# Robot-Controller_v11.net
KiCad netlist of a schematic drawn in EAGLE
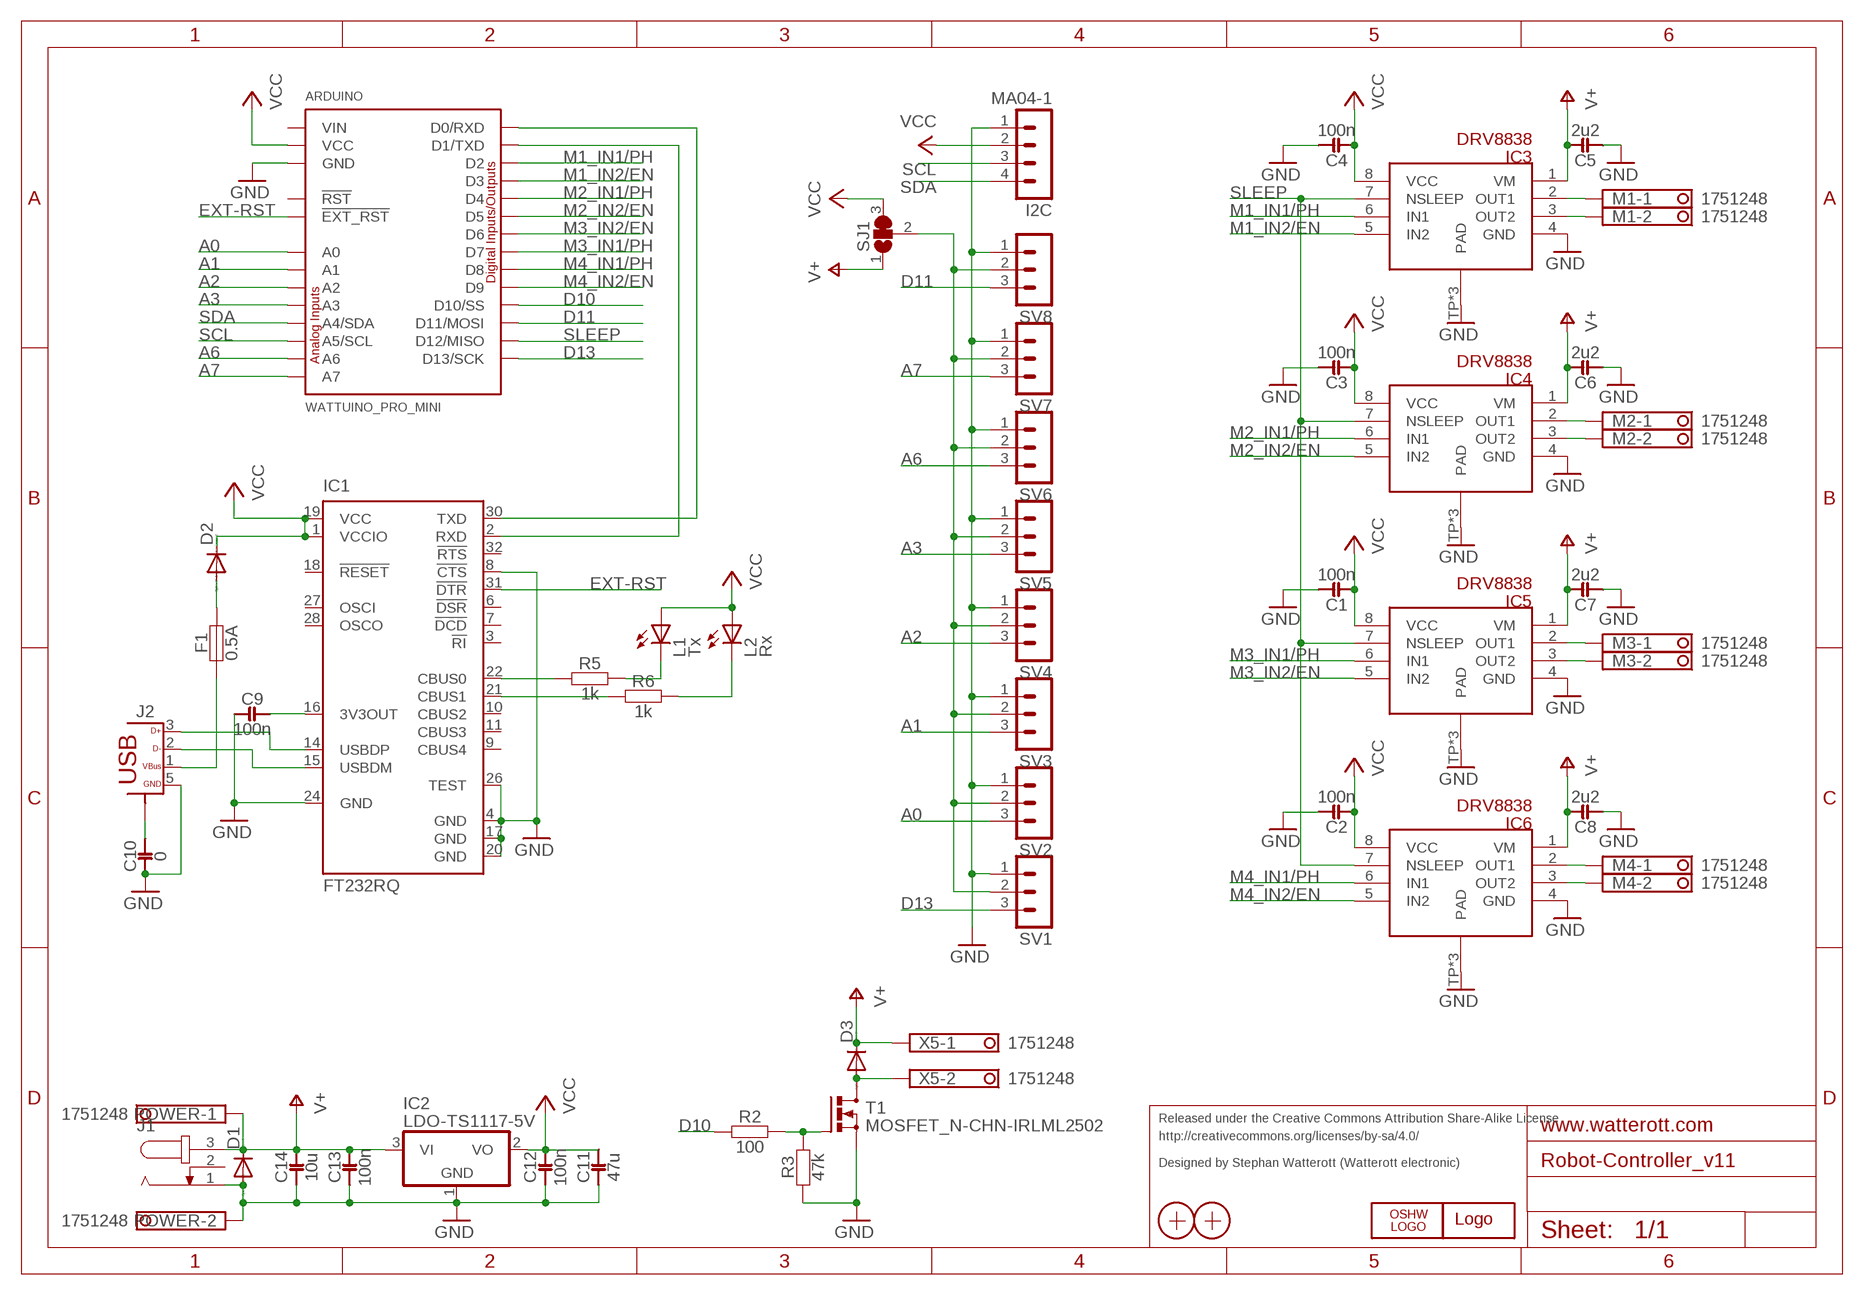
[diagram p0: schematic, sheet 1]

(export (version "E")
  (design (tool "Eeschema 10.0.6"))
  (components
    (comp (ref "ARDUINO")
      (value "WATTUINO_PRO_MINI")
      (footprint "eagle-import:WATTUINO_PRO_MINI")
      (libsource (lib "eagle-import") (part "WATTUINO_PRO_MINIADV1.05"))
    )
    (comp (ref "C1")
      (value "100n")
      (footprint "eagle-import:R0603")
      (libsource (lib "eagle-import") (part "CAPACITOR-C0603"))
    )
    (comp (ref "C2")
      (value "100n")
      (footprint "eagle-import:R0603")
      (libsource (lib "eagle-import") (part "CAPACITOR-C0603"))
    )
    (comp (ref "C3")
      (value "100n")
      (footprint "eagle-import:R0603")
      (libsource (lib "eagle-import") (part "CAPACITOR-C0603"))
    )
    (comp (ref "C4")
      (value "100n")
      (footprint "eagle-import:R0603")
      (libsource (lib "eagle-import") (part "CAPACITOR-C0603"))
    )
    (comp (ref "C5")
      (value "2u2")
      (footprint "eagle-import:R0603")
      (libsource (lib "eagle-import") (part "CAPACITOR-C0603"))
    )
    (comp (ref "C6")
      (value "2u2")
      (footprint "eagle-import:R0603")
      (libsource (lib "eagle-import") (part "CAPACITOR-C0603"))
    )
    (comp (ref "C7")
      (value "2u2")
      (footprint "eagle-import:R0603")
      (libsource (lib "eagle-import") (part "CAPACITOR-C0603"))
    )
    (comp (ref "C8")
      (value "2u2")
      (footprint "eagle-import:R0603")
      (libsource (lib "eagle-import") (part "CAPACITOR-C0603"))
    )
    (comp (ref "C9")
      (value "100n")
      (footprint "eagle-import:R0603")
      (libsource (lib "eagle-import") (part "CAPACITOR-C0603"))
    )
    (comp (ref "C10")
      (value "0")
      (footprint "eagle-import:R0603")
      (libsource (lib "eagle-import") (part "CAPACITOR-C0603"))
    )
    (comp (ref "C11")
      (value "47u")
      (footprint "eagle-import:R1206")
      (libsource (lib "eagle-import") (part "CAPACITOR-C1206"))
    )
    (comp (ref "C12")
      (value "100n")
      (footprint "eagle-import:R0603")
      (libsource (lib "eagle-import") (part "CAPACITOR-C0603"))
    )
    (comp (ref "C13")
      (value "100n")
      (footprint "eagle-import:R0603")
      (libsource (lib "eagle-import") (part "CAPACITOR-C0603"))
    )
    (comp (ref "C14")
      (value "10u")
      (footprint "eagle-import:R1206")
      (libsource (lib "eagle-import") (part "CAPACITOR-C1206"))
    )
    (comp (ref "D1")
      (value "CGRM4001-G")
      (footprint "eagle-import:SOD-123_MINI-SMA")
      (libsource (lib "eagle-import") (part "CGRM400-G1"))
    )
    (comp (ref "D2")
      (value "CGRM4001-G")
      (footprint "eagle-import:SOD-123_MINI-SMA")
      (libsource (lib "eagle-import") (part "CGRM400-G1"))
    )
    (comp (ref "D3")
      (value "CGRM4001-G")
      (footprint "eagle-import:SOD-123_MINI-SMA")
      (libsource (lib "eagle-import") (part "CGRM400-G1"))
    )
    (comp (ref "F1")
      (value "0.5A")
      (footprint "eagle-import:R0805")
      (libsource (lib "eagle-import") (part "RESISTOR-R0805"))
    )
    (comp (ref "I2C")
      (value "MA04-1")
      (footprint "eagle-import:MA04-1")
      (libsource (lib "eagle-import") (part "MA04-1"))
    )
    (comp (ref "IC1")
      (value "FT232RQ")
      (footprint "eagle-import:QFN32")
      (libsource (lib "eagle-import") (part "FT232RQ"))
    )
    (comp (ref "IC2")
      (value "LDO-TS1117-5V")
      (footprint "eagle-import:SOT223")
      (libsource (lib "eagle-import") (part "LDO-TS1117"))
    )
    (comp (ref "IC3")
      (value "DRV8838")
      (footprint "eagle-import:WSON8")
      (libsource (lib "eagle-import") (part "DRV8837"))
    )
    (comp (ref "IC4")
      (value "DRV8838")
      (footprint "eagle-import:WSON8")
      (libsource (lib "eagle-import") (part "DRV8837"))
    )
    (comp (ref "IC5")
      (value "DRV8838")
      (footprint "eagle-import:WSON8")
      (libsource (lib "eagle-import") (part "DRV8837"))
    )
    (comp (ref "IC6")
      (value "DRV8838")
      (footprint "eagle-import:WSON8")
      (libsource (lib "eagle-import") (part "DRV8837"))
    )
    (comp (ref "J1")
      (value "DC-JACK\"\"")
      (footprint "eagle-import:DC-JACK")
      (libsource (lib "eagle-import") (part "DC-JACK{dblquote}{dblquote}"))
    )
    (comp (ref "J2")
      (value "USB10103594-0001LF")
      (footprint "eagle-import:10103594")
      (libsource (lib "eagle-import") (part "USB10103594-0001LF"))
    )
    (comp (ref "L1")
      (value "Tx")
      (footprint "eagle-import:LED_0603")
      (libsource (lib "eagle-import") (part "LED-0603"))
    )
    (comp (ref "L2")
      (value "Rx")
      (footprint "eagle-import:LED_0603")
      (libsource (lib "eagle-import") (part "LED-0603"))
    )
    (comp (ref "LOGO2")
      (value "OSHW_LOGOX0100")
      (footprint "eagle-import:OSHW_6X100")
      (libsource (lib "eagle-import") (part "OSHW_LOGOX0100"))
    )
    (comp (ref "LOGO3")
      (value "LOGO-SPARK_PLACE")
      (footprint "eagle-import:SPARK_TPLACE")
      (libsource (lib "eagle-import") (part "LOGO-SPARK_PLACE"))
    )
    (comp (ref "M1")
      (value "1751248")
      (footprint "eagle-import:1751248")
      (libsource (lib "eagle-import") (part "1751248"))
    )
    (comp (ref "M2")
      (value "1751248")
      (footprint "eagle-import:1751248")
      (libsource (lib "eagle-import") (part "1751248"))
    )
    (comp (ref "M3")
      (value "1751248")
      (footprint "eagle-import:1751248")
      (libsource (lib "eagle-import") (part "1751248"))
    )
    (comp (ref "M4")
      (value "1751248")
      (footprint "eagle-import:1751248")
      (libsource (lib "eagle-import") (part "1751248"))
    )
    (comp (ref "POWER")
      (value "1751248")
      (footprint "eagle-import:1751248")
      (libsource (lib "eagle-import") (part "1751248"))
    )
    (comp (ref "R2")
      (value "100")
      (footprint "eagle-import:R0603")
      (libsource (lib "eagle-import") (part "RESISTOR-R0603"))
    )
    (comp (ref "R3")
      (value "47k")
      (footprint "eagle-import:R0603")
      (libsource (lib "eagle-import") (part "RESISTOR-R0603"))
    )
    (comp (ref "R5")
      (value "1k")
      (footprint "eagle-import:R0603")
      (libsource (lib "eagle-import") (part "RESISTOR-R0603"))
    )
    (comp (ref "R6")
      (value "1k")
      (footprint "eagle-import:R0603")
      (libsource (lib "eagle-import") (part "RESISTOR-R0603"))
    )
    (comp (ref "SJ1")
      (value "SJ2W")
      (footprint "eagle-import:SJ_2")
      (libsource (lib "eagle-import") (part "SJ2W"))
    )
    (comp (ref "SV1")
      (value "MA03-1")
      (footprint "eagle-import:MA03-1")
      (libsource (lib "eagle-import") (part "MA03-1"))
    )
    (comp (ref "SV2")
      (value "MA03-1")
      (footprint "eagle-import:MA03-1")
      (libsource (lib "eagle-import") (part "MA03-1"))
    )
    (comp (ref "SV3")
      (value "MA03-1")
      (footprint "eagle-import:MA03-1")
      (libsource (lib "eagle-import") (part "MA03-1"))
    )
    (comp (ref "SV4")
      (value "MA03-1")
      (footprint "eagle-import:MA03-1")
      (libsource (lib "eagle-import") (part "MA03-1"))
    )
    (comp (ref "SV5")
      (value "MA03-1")
      (footprint "eagle-import:MA03-1")
      (libsource (lib "eagle-import") (part "MA03-1"))
    )
    (comp (ref "SV6")
      (value "MA03-1")
      (footprint "eagle-import:MA03-1")
      (libsource (lib "eagle-import") (part "MA03-1"))
    )
    (comp (ref "SV7")
      (value "MA03-1")
      (footprint "eagle-import:MA03-1")
      (libsource (lib "eagle-import") (part "MA03-1"))
    )
    (comp (ref "SV8")
      (value "MA03-1")
      (footprint "eagle-import:MA03-1")
      (libsource (lib "eagle-import") (part "MA03-1"))
    )
    (comp (ref "T1")
      (value "MOSFET_N-CHN-IRLML2502")
      (footprint "eagle-import:SOT23")
      (libsource (lib "eagle-import") (part "MOSFET_N-CHN-IRLML2502"))
    )
    (comp (ref "X1")
      (value "PASSER-07")
      (footprint "eagle-import:PASSER_07MM")
      (libsource (lib "eagle-import") (part "PASSER-07"))
    )
    (comp (ref "X2")
      (value "PASSER-07")
      (footprint "eagle-import:PASSER_07MM")
      (libsource (lib "eagle-import") (part "PASSER-07"))
    )
    (comp (ref "X5")
      (value "1751248")
      (footprint "eagle-import:1751248")
      (libsource (lib "eagle-import") (part "1751248"))
    )
  )
  (nets
    (net (code "1") (name "/A0") (class "Default")
      (node (ref "ARDUINO") (pin "A0") (pinfunction "A0_A0") (pintype "input"))
      (node (ref "SV2") (pin "3") (pinfunction "3_3") (pintype "passive"))
    )
    (net (code "2") (name "/A1") (class "Default")
      (node (ref "ARDUINO") (pin "A1") (pinfunction "A1_A1") (pintype "input"))
      (node (ref "SV3") (pin "3") (pinfunction "3_3") (pintype "passive"))
    )
    (net (code "3") (name "/A2") (class "Default")
      (node (ref "ARDUINO") (pin "A2") (pinfunction "A2_A2") (pintype "input"))
      (node (ref "SV4") (pin "3") (pinfunction "3_3") (pintype "passive"))
    )
    (net (code "4") (name "/A3") (class "Default")
      (node (ref "ARDUINO") (pin "A3") (pinfunction "A3_A3") (pintype "input"))
      (node (ref "SV5") (pin "3") (pinfunction "3_3") (pintype "passive"))
    )
    (net (code "5") (name "/A6") (class "Default")
      (node (ref "ARDUINO") (pin "A6") (pinfunction "A6_A6") (pintype "input"))
      (node (ref "SV6") (pin "3") (pinfunction "3_3") (pintype "passive"))
    )
    (net (code "6") (name "/A7") (class "Default")
      (node (ref "ARDUINO") (pin "A7") (pinfunction "A7_A7") (pintype "input"))
      (node (ref "SV7") (pin "3") (pinfunction "3_3") (pintype "passive"))
    )
    (net (code "7") (name "/D10") (class "Default")
      (node (ref "ARDUINO") (pin "10") (pinfunction "D10/SS_10") (pintype "bidirectional"))
      (node (ref "R2") (pin "1") (pinfunction "1_1") (pintype "passive"))
    )
    (net (code "8") (name "/D11") (class "Default")
      (node (ref "ARDUINO") (pin "11") (pinfunction "D11/MOSI_11") (pintype "bidirectional"))
      (node (ref "SV8") (pin "3") (pinfunction "3_3") (pintype "passive"))
    )
    (net (code "9") (name "/D13") (class "Default")
      (node (ref "ARDUINO") (pin "13") (pinfunction "D13/SCK_13") (pintype "bidirectional"))
      (node (ref "SV1") (pin "3") (pinfunction "3_3") (pintype "passive"))
    )
    (net (code "10") (name "/EXT-RST") (class "Default")
      (node (ref "ARDUINO") (pin "EXT_RST") (pinfunction "~{EXT_RST}_EXT_RST") (pintype "bidirectional"))
      (node (ref "IC1") (pin "31") (pinfunction "~{DTR}_31") (pintype "output"))
    )
    (net (code "11") (name "/M1_IN1{slash}PH") (class "Default")
      (node (ref "ARDUINO") (pin "2") (pinfunction "D2_2") (pintype "bidirectional"))
      (node (ref "IC3") (pin "6") (pinfunction "IN1_6") (pintype "bidirectional"))
    )
    (net (code "12") (name "/M1_IN2{slash}EN") (class "Default")
      (node (ref "ARDUINO") (pin "3") (pinfunction "D3_3") (pintype "bidirectional"))
      (node (ref "IC3") (pin "5") (pinfunction "IN2_5") (pintype "bidirectional"))
    )
    (net (code "13") (name "/M2_IN1{slash}PH") (class "Default")
      (node (ref "ARDUINO") (pin "4") (pinfunction "D4_4") (pintype "bidirectional"))
      (node (ref "IC4") (pin "6") (pinfunction "IN1_6") (pintype "bidirectional"))
    )
    (net (code "14") (name "/M2_IN2{slash}EN") (class "Default")
      (node (ref "ARDUINO") (pin "5") (pinfunction "D5_5") (pintype "bidirectional"))
      (node (ref "IC4") (pin "5") (pinfunction "IN2_5") (pintype "bidirectional"))
    )
    (net (code "15") (name "/M3_IN1{slash}PH") (class "Default")
      (node (ref "ARDUINO") (pin "7") (pinfunction "D7_7") (pintype "bidirectional"))
      (node (ref "IC5") (pin "6") (pinfunction "IN1_6") (pintype "bidirectional"))
    )
    (net (code "16") (name "/M3_IN2{slash}EN") (class "Default")
      (node (ref "ARDUINO") (pin "6") (pinfunction "D6_6") (pintype "bidirectional"))
      (node (ref "IC5") (pin "5") (pinfunction "IN2_5") (pintype "bidirectional"))
    )
    (net (code "17") (name "/M4_IN1{slash}PH") (class "Default")
      (node (ref "ARDUINO") (pin "8") (pinfunction "D8_8") (pintype "bidirectional"))
      (node (ref "IC6") (pin "6") (pinfunction "IN1_6") (pintype "bidirectional"))
    )
    (net (code "18") (name "/M4_IN2{slash}EN") (class "Default")
      (node (ref "ARDUINO") (pin "9") (pinfunction "D9_9") (pintype "bidirectional"))
      (node (ref "IC6") (pin "5") (pinfunction "IN2_5") (pintype "bidirectional"))
    )
    (net (code "19") (name "/SCL") (class "Default")
      (node (ref "ARDUINO") (pin "A5") (pinfunction "A5/SCL_A5") (pintype "input"))
      (node (ref "I2C") (pin "3") (pinfunction "3_3") (pintype "passive"))
    )
    (net (code "20") (name "/SDA") (class "Default")
      (node (ref "ARDUINO") (pin "A4") (pinfunction "A4/SDA_A4") (pintype "input"))
      (node (ref "I2C") (pin "4") (pinfunction "4_4") (pintype "passive"))
    )
    (net (code "21") (name "/SLEEP") (class "Default")
      (node (ref "ARDUINO") (pin "12") (pinfunction "D12/MISO_12") (pintype "bidirectional"))
      (node (ref "IC3") (pin "7") (pinfunction "NSLEEP_7") (pintype "bidirectional"))
      (node (ref "IC4") (pin "7") (pinfunction "NSLEEP_7") (pintype "bidirectional"))
      (node (ref "IC5") (pin "7") (pinfunction "NSLEEP_7") (pintype "bidirectional"))
      (node (ref "IC6") (pin "7") (pinfunction "NSLEEP_7") (pintype "bidirectional"))
    )
    (net (code "22") (name "/VIN") (class "Default")
      (node (ref "ARDUINO") (pin "VIN") (pinfunction "VIN_VIN") (pintype "power_in"))
    )
    (net (code "23") (name "GND") (class "Default")
      (node (ref "ARDUINO") (pin "GND@1") (pinfunction "GND_GND@1") (pintype "power_in"))
      (node (ref "C1") (pin "2") (pinfunction "2_2") (pintype "passive"))
      (node (ref "C10") (pin "1") (pinfunction "1_1") (pintype "passive"))
      (node (ref "C11") (pin "1") (pinfunction "1_1") (pintype "passive"))
      (node (ref "C12") (pin "1") (pinfunction "1_1") (pintype "passive"))
      (node (ref "C13") (pin "1") (pinfunction "1_1") (pintype "passive"))
      (node (ref "C14") (pin "1") (pinfunction "1_1") (pintype "passive"))
      (node (ref "C2") (pin "2") (pinfunction "2_2") (pintype "passive"))
      (node (ref "C3") (pin "2") (pinfunction "2_2") (pintype "passive"))
      (node (ref "C4") (pin "2") (pinfunction "2_2") (pintype "passive"))
      (node (ref "C5") (pin "1") (pinfunction "1_1") (pintype "passive"))
      (node (ref "C6") (pin "1") (pinfunction "1_1") (pintype "passive"))
      (node (ref "C7") (pin "1") (pinfunction "1_1") (pintype "passive"))
      (node (ref "C8") (pin "1") (pinfunction "1_1") (pintype "passive"))
      (node (ref "C9") (pin "1") (pinfunction "1_1") (pintype "passive"))
      (node (ref "D1") (pin "A") (pinfunction "A_A") (pintype "passive"))
      (node (ref "I2C") (pin "1") (pinfunction "1_1") (pintype "passive"))
      (node (ref "IC1") (pin "17") (pinfunction "GND_17") (pintype "power_in"))
      (node (ref "IC1") (pin "20") (pinfunction "GND_20") (pintype "power_in"))
      (node (ref "IC1") (pin "24") (pinfunction "GND_24") (pintype "power_in"))
      (node (ref "IC1") (pin "26") (pinfunction "TEST_26") (pintype "input"))
      (node (ref "IC1") (pin "4") (pinfunction "GND_4") (pintype "power_in"))
      (node (ref "IC1") (pin "8") (pinfunction "~{CTS}_8") (pintype "input"))
      (node (ref "IC2") (pin "1") (pinfunction "GND_1") (pintype "passive"))
      (node (ref "IC3") (pin "4") (pinfunction "GND_4") (pintype "bidirectional"))
      (node (ref "IC3") (pin "TP") (pinfunction "PAD_TP") (pintype "bidirectional"))
      (node (ref "IC3") (pin "TP1") (pinfunction "PAD_TP1") (pintype "bidirectional"))
      (node (ref "IC3") (pin "TP2") (pinfunction "PAD_TP2") (pintype "bidirectional"))
      (node (ref "IC4") (pin "4") (pinfunction "GND_4") (pintype "bidirectional"))
      (node (ref "IC4") (pin "TP") (pinfunction "PAD_TP") (pintype "bidirectional"))
      (node (ref "IC4") (pin "TP1") (pinfunction "PAD_TP1") (pintype "bidirectional"))
      (node (ref "IC4") (pin "TP2") (pinfunction "PAD_TP2") (pintype "bidirectional"))
      (node (ref "IC5") (pin "4") (pinfunction "GND_4") (pintype "bidirectional"))
      (node (ref "IC5") (pin "TP") (pinfunction "PAD_TP") (pintype "bidirectional"))
      (node (ref "IC5") (pin "TP1") (pinfunction "PAD_TP1") (pintype "bidirectional"))
      (node (ref "IC5") (pin "TP2") (pinfunction "PAD_TP2") (pintype "bidirectional"))
      (node (ref "IC6") (pin "4") (pinfunction "GND_4") (pintype "bidirectional"))
      (node (ref "IC6") (pin "TP") (pinfunction "PAD_TP") (pintype "bidirectional"))
      (node (ref "IC6") (pin "TP1") (pinfunction "PAD_TP1") (pintype "bidirectional"))
      (node (ref "IC6") (pin "TP2") (pinfunction "PAD_TP2") (pintype "bidirectional"))
      (node (ref "J1") (pin "1") (pinfunction "1_1") (pintype "passive"))
      (node (ref "J2") (pin "5") (pinfunction "GND_5") (pintype "bidirectional"))
      (node (ref "POWER") (pin "2") (pinfunction "K_2") (pintype "passive"))
      (node (ref "R3") (pin "1") (pinfunction "1_1") (pintype "passive"))
      (node (ref "SV1") (pin "1") (pinfunction "1_1") (pintype "passive"))
      (node (ref "SV2") (pin "1") (pinfunction "1_1") (pintype "passive"))
      (node (ref "SV3") (pin "1") (pinfunction "1_1") (pintype "passive"))
      (node (ref "SV4") (pin "1") (pinfunction "1_1") (pintype "passive"))
      (node (ref "SV5") (pin "1") (pinfunction "1_1") (pintype "passive"))
      (node (ref "SV6") (pin "1") (pinfunction "1_1") (pintype "passive"))
      (node (ref "SV7") (pin "1") (pinfunction "1_1") (pintype "passive"))
      (node (ref "SV8") (pin "1") (pinfunction "1_1") (pintype "passive"))
      (node (ref "T1") (pin "2") (pinfunction "S_2") (pintype "passive"))
    )
    (net (code "24") (name "Net-(ARDUINO-D0{slash}RXD)") (class "Default")
      (node (ref "ARDUINO") (pin "RXD@1") (pinfunction "D0/RXD_RXD@1") (pintype "bidirectional"))
      (node (ref "IC1") (pin "30") (pinfunction "TXD_30") (pintype "output"))
    )
    (net (code "25") (name "Net-(ARDUINO-D1{slash}TXD)") (class "Default")
      (node (ref "ARDUINO") (pin "TXD@1") (pinfunction "D1/TXD_TXD@1") (pintype "bidirectional"))
      (node (ref "IC1") (pin "2") (pinfunction "RXD_2") (pintype "input"))
    )
    (net (code "26") (name "Net-(C10-Pad2)") (class "Default")
      (node (ref "C10") (pin "2") (pinfunction "2_2") (pintype "passive"))
      (node (ref "J2") (pin "P$6") (pinfunction "SHIELD_P$6") (pintype "bidirectional"))
      (node (ref "J2") (pin "P$7") (pinfunction "SHIELD_P$7") (pintype "bidirectional"))
    )
    (net (code "27") (name "Net-(D2-PadA)") (class "Default")
      (node (ref "D2") (pin "A") (pinfunction "A_A") (pintype "passive"))
      (node (ref "F1") (pin "2") (pinfunction "2_2") (pintype "passive"))
    )
    (net (code "28") (name "Net-(IC1-3V3OUT)") (class "Default")
      (node (ref "C9") (pin "2") (pinfunction "2_2") (pintype "passive"))
      (node (ref "IC1") (pin "16") (pinfunction "3V3OUT_16") (pintype "output"))
    )
    (net (code "29") (name "Net-(IC1-CBUS0)") (class "Default")
      (node (ref "IC1") (pin "22") (pinfunction "CBUS0_22") (pintype "bidirectional"))
      (node (ref "R5") (pin "1") (pinfunction "1_1") (pintype "passive"))
    )
    (net (code "30") (name "Net-(IC1-CBUS1)") (class "Default")
      (node (ref "IC1") (pin "21") (pinfunction "CBUS1_21") (pintype "bidirectional"))
      (node (ref "R6") (pin "1") (pinfunction "1_1") (pintype "passive"))
    )
    (net (code "31") (name "Net-(IC1-USBDM)") (class "Default")
      (node (ref "IC1") (pin "15") (pinfunction "USBDM_15") (pintype "bidirectional"))
      (node (ref "J2") (pin "2") (pinfunction "D-_2") (pintype "bidirectional"))
    )
    (net (code "32") (name "Net-(IC1-USBDP)") (class "Default")
      (node (ref "IC1") (pin "14") (pinfunction "USBDP_14") (pintype "bidirectional"))
      (node (ref "J2") (pin "3") (pinfunction "D+_3") (pintype "bidirectional"))
    )
    (net (code "33") (name "Net-(IC3-OUT1)") (class "Default")
      (node (ref "IC3") (pin "2") (pinfunction "OUT1_2") (pintype "bidirectional"))
      (node (ref "M1") (pin "1") (pinfunction "K_1") (pintype "passive"))
    )
    (net (code "34") (name "Net-(IC3-OUT2)") (class "Default")
      (node (ref "IC3") (pin "3") (pinfunction "OUT2_3") (pintype "bidirectional"))
      (node (ref "M1") (pin "2") (pinfunction "K_2") (pintype "passive"))
    )
    (net (code "35") (name "Net-(IC4-OUT1)") (class "Default")
      (node (ref "IC4") (pin "2") (pinfunction "OUT1_2") (pintype "bidirectional"))
      (node (ref "M2") (pin "1") (pinfunction "K_1") (pintype "passive"))
    )
    (net (code "36") (name "Net-(IC4-OUT2)") (class "Default")
      (node (ref "IC4") (pin "3") (pinfunction "OUT2_3") (pintype "bidirectional"))
      (node (ref "M2") (pin "2") (pinfunction "K_2") (pintype "passive"))
    )
    (net (code "37") (name "Net-(IC5-OUT1)") (class "Default")
      (node (ref "IC5") (pin "2") (pinfunction "OUT1_2") (pintype "bidirectional"))
      (node (ref "M3") (pin "1") (pinfunction "K_1") (pintype "passive"))
    )
    (net (code "38") (name "Net-(IC5-OUT2)") (class "Default")
      (node (ref "IC5") (pin "3") (pinfunction "OUT2_3") (pintype "bidirectional"))
      (node (ref "M3") (pin "2") (pinfunction "K_2") (pintype "passive"))
    )
    (net (code "39") (name "Net-(IC6-OUT1)") (class "Default")
      (node (ref "IC6") (pin "2") (pinfunction "OUT1_2") (pintype "bidirectional"))
      (node (ref "M4") (pin "1") (pinfunction "K_1") (pintype "passive"))
    )
    (net (code "40") (name "Net-(IC6-OUT2)") (class "Default")
      (node (ref "IC6") (pin "3") (pinfunction "OUT2_3") (pintype "bidirectional"))
      (node (ref "M4") (pin "2") (pinfunction "K_2") (pintype "passive"))
    )
    (net (code "41") (name "Net-(J2-VBUS)") (class "Default")
      (node (ref "F1") (pin "1") (pinfunction "1_1") (pintype "passive"))
      (node (ref "J2") (pin "1") (pinfunction "VBUS_1") (pintype "bidirectional"))
    )
    (net (code "42") (name "Net-(L1-PadC)") (class "Default")
      (node (ref "L1") (pin "C") (pinfunction "C_C") (pintype "passive"))
      (node (ref "R5") (pin "2") (pinfunction "2_2") (pintype "passive"))
    )
    (net (code "43") (name "Net-(L2-PadC)") (class "Default")
      (node (ref "L2") (pin "C") (pinfunction "C_C") (pintype "passive"))
      (node (ref "R6") (pin "2") (pinfunction "2_2") (pintype "passive"))
    )
    (net (code "44") (name "Net-(SJ1-Pad2)") (class "Default")
      (node (ref "SJ1") (pin "2") (pinfunction "2_2") (pintype "passive"))
      (node (ref "SV1") (pin "2") (pinfunction "2_2") (pintype "passive"))
      (node (ref "SV2") (pin "2") (pinfunction "2_2") (pintype "passive"))
      (node (ref "SV3") (pin "2") (pinfunction "2_2") (pintype "passive"))
      (node (ref "SV4") (pin "2") (pinfunction "2_2") (pintype "passive"))
      (node (ref "SV5") (pin "2") (pinfunction "2_2") (pintype "passive"))
      (node (ref "SV6") (pin "2") (pinfunction "2_2") (pintype "passive"))
      (node (ref "SV7") (pin "2") (pinfunction "2_2") (pintype "passive"))
      (node (ref "SV8") (pin "2") (pinfunction "2_2") (pintype "passive"))
    )
    (net (code "45") (name "Net-(T1-D)") (class "Default")
      (node (ref "D3") (pin "A") (pinfunction "A_A") (pintype "passive"))
      (node (ref "T1") (pin "3") (pinfunction "D_3") (pintype "passive"))
      (node (ref "X5") (pin "2") (pinfunction "K_2") (pintype "passive"))
    )
    (net (code "46") (name "Net-(T1-G)") (class "Default")
      (node (ref "R2") (pin "2") (pinfunction "2_2") (pintype "passive"))
      (node (ref "R3") (pin "2") (pinfunction "2_2") (pintype "passive"))
      (node (ref "T1") (pin "1") (pinfunction "G_1") (pintype "passive"))
    )
    (net (code "47") (name "V+") (class "Default")
      (node (ref "C13") (pin "2") (pinfunction "2_2") (pintype "passive"))
      (node (ref "C14") (pin "2") (pinfunction "2_2") (pintype "passive"))
      (node (ref "C5") (pin "2") (pinfunction "2_2") (pintype "passive"))
      (node (ref "C6") (pin "2") (pinfunction "2_2") (pintype "passive"))
      (node (ref "C7") (pin "2") (pinfunction "2_2") (pintype "passive"))
      (node (ref "C8") (pin "2") (pinfunction "2_2") (pintype "passive"))
      (node (ref "D1") (pin "C") (pinfunction "C_C") (pintype "passive"))
      (node (ref "D3") (pin "C") (pinfunction "C_C") (pintype "passive"))
      (node (ref "IC2") (pin "3") (pinfunction "VI_3") (pintype "input"))
      (node (ref "IC3") (pin "1") (pinfunction "VM_1") (pintype "bidirectional"))
      (node (ref "IC4") (pin "1") (pinfunction "VM_1") (pintype "bidirectional"))
      (node (ref "IC5") (pin "1") (pinfunction "VM_1") (pintype "bidirectional"))
      (node (ref "IC6") (pin "1") (pinfunction "VM_1") (pintype "bidirectional"))
      (node (ref "J1") (pin "3") (pinfunction "3_3") (pintype "passive"))
      (node (ref "POWER") (pin "1") (pinfunction "K_1") (pintype "passive"))
      (node (ref "SJ1") (pin "1") (pinfunction "1_1") (pintype "passive"))
      (node (ref "X5") (pin "1") (pinfunction "K_1") (pintype "passive"))
    )
    (net (code "48") (name "VCC") (class "Default")
      (node (ref "ARDUINO") (pin "VCC@1") (pinfunction "VCC_VCC@1") (pintype "power_in"))
      (node (ref "C1") (pin "1") (pinfunction "1_1") (pintype "passive"))
      (node (ref "C11") (pin "2") (pinfunction "2_2") (pintype "passive"))
      (node (ref "C12") (pin "2") (pinfunction "2_2") (pintype "passive"))
      (node (ref "C2") (pin "1") (pinfunction "1_1") (pintype "passive"))
      (node (ref "C3") (pin "1") (pinfunction "1_1") (pintype "passive"))
      (node (ref "C4") (pin "1") (pinfunction "1_1") (pintype "passive"))
      (node (ref "D2") (pin "C") (pinfunction "C_C") (pintype "passive"))
      (node (ref "I2C") (pin "2") (pinfunction "2_2") (pintype "passive"))
      (node (ref "IC1") (pin "1") (pinfunction "VCCIO_1") (pintype "power_in"))
      (node (ref "IC1") (pin "19") (pinfunction "VCC_19") (pintype "power_in"))
      (node (ref "IC2") (pin "2") (pinfunction "VO_2") (pintype "passive"))
      (node (ref "IC3") (pin "8") (pinfunction "VCC_8") (pintype "bidirectional"))
      (node (ref "IC4") (pin "8") (pinfunction "VCC_8") (pintype "bidirectional"))
      (node (ref "IC5") (pin "8") (pinfunction "VCC_8") (pintype "bidirectional"))
      (node (ref "IC6") (pin "8") (pinfunction "VCC_8") (pintype "bidirectional"))
      (node (ref "L1") (pin "A") (pinfunction "A_A") (pintype "passive"))
      (node (ref "L2") (pin "A") (pinfunction "A_A") (pintype "passive"))
      (node (ref "SJ1") (pin "3") (pinfunction "3_3") (pintype "passive"))
    )
    (net (code "49") (name "unconnected-(ARDUINO-~{RST}-PadRST@1)") (class "Default")
      (node (ref "ARDUINO") (pin "RST@1") (pinfunction "~{RST}_RST@1") (pintype "input"))
    )
    (net (code "50") (name "unconnected-(IC1-CBUS2-Pad10)") (class "Default")
      (node (ref "IC1") (pin "10") (pinfunction "CBUS2_10") (pintype "bidirectional"))
    )
    (net (code "51") (name "unconnected-(IC1-CBUS3-Pad11)") (class "Default")
      (node (ref "IC1") (pin "11") (pinfunction "CBUS3_11") (pintype "bidirectional"))
    )
    (net (code "52") (name "unconnected-(IC1-CBUS4-Pad9)") (class "Default")
      (node (ref "IC1") (pin "9") (pinfunction "CBUS4_9") (pintype "bidirectional"))
    )
    (net (code "53") (name "unconnected-(IC1-OSCI-Pad27)") (class "Default")
      (node (ref "IC1") (pin "27") (pinfunction "OSCI_27") (pintype "input"))
    )
    (net (code "54") (name "unconnected-(IC1-OSCO-Pad28)") (class "Default")
      (node (ref "IC1") (pin "28") (pinfunction "OSCO_28") (pintype "output"))
    )
    (net (code "55") (name "unconnected-(IC1-~{DCD}-Pad7)") (class "Default")
      (node (ref "IC1") (pin "7") (pinfunction "~{DCD}_7") (pintype "input"))
    )
    (net (code "56") (name "unconnected-(IC1-~{DSR}-Pad6)") (class "Default")
      (node (ref "IC1") (pin "6") (pinfunction "~{DSR}_6") (pintype "input"))
    )
    (net (code "57") (name "unconnected-(IC1-~{RESET}-Pad18)") (class "Default")
      (node (ref "IC1") (pin "18") (pinfunction "~{RESET}_18") (pintype "input"))
    )
    (net (code "58") (name "unconnected-(IC1-~{RI}-Pad3)") (class "Default")
      (node (ref "IC1") (pin "3") (pinfunction "~{RI}_3") (pintype "input"))
    )
    (net (code "59") (name "unconnected-(IC1-~{RTS}-Pad32)") (class "Default")
      (node (ref "IC1") (pin "32") (pinfunction "~{RTS}_32") (pintype "output"))
    )
    (net (code "60") (name "unconnected-(J1-Pad2)") (class "Default")
      (node (ref "J1") (pin "2") (pinfunction "2_2") (pintype "passive"))
    )
  )
)
